# FPGA_Banks_44_45_46_DDR64.net
KiCad netlist of a schematic drawn in Altium Designer
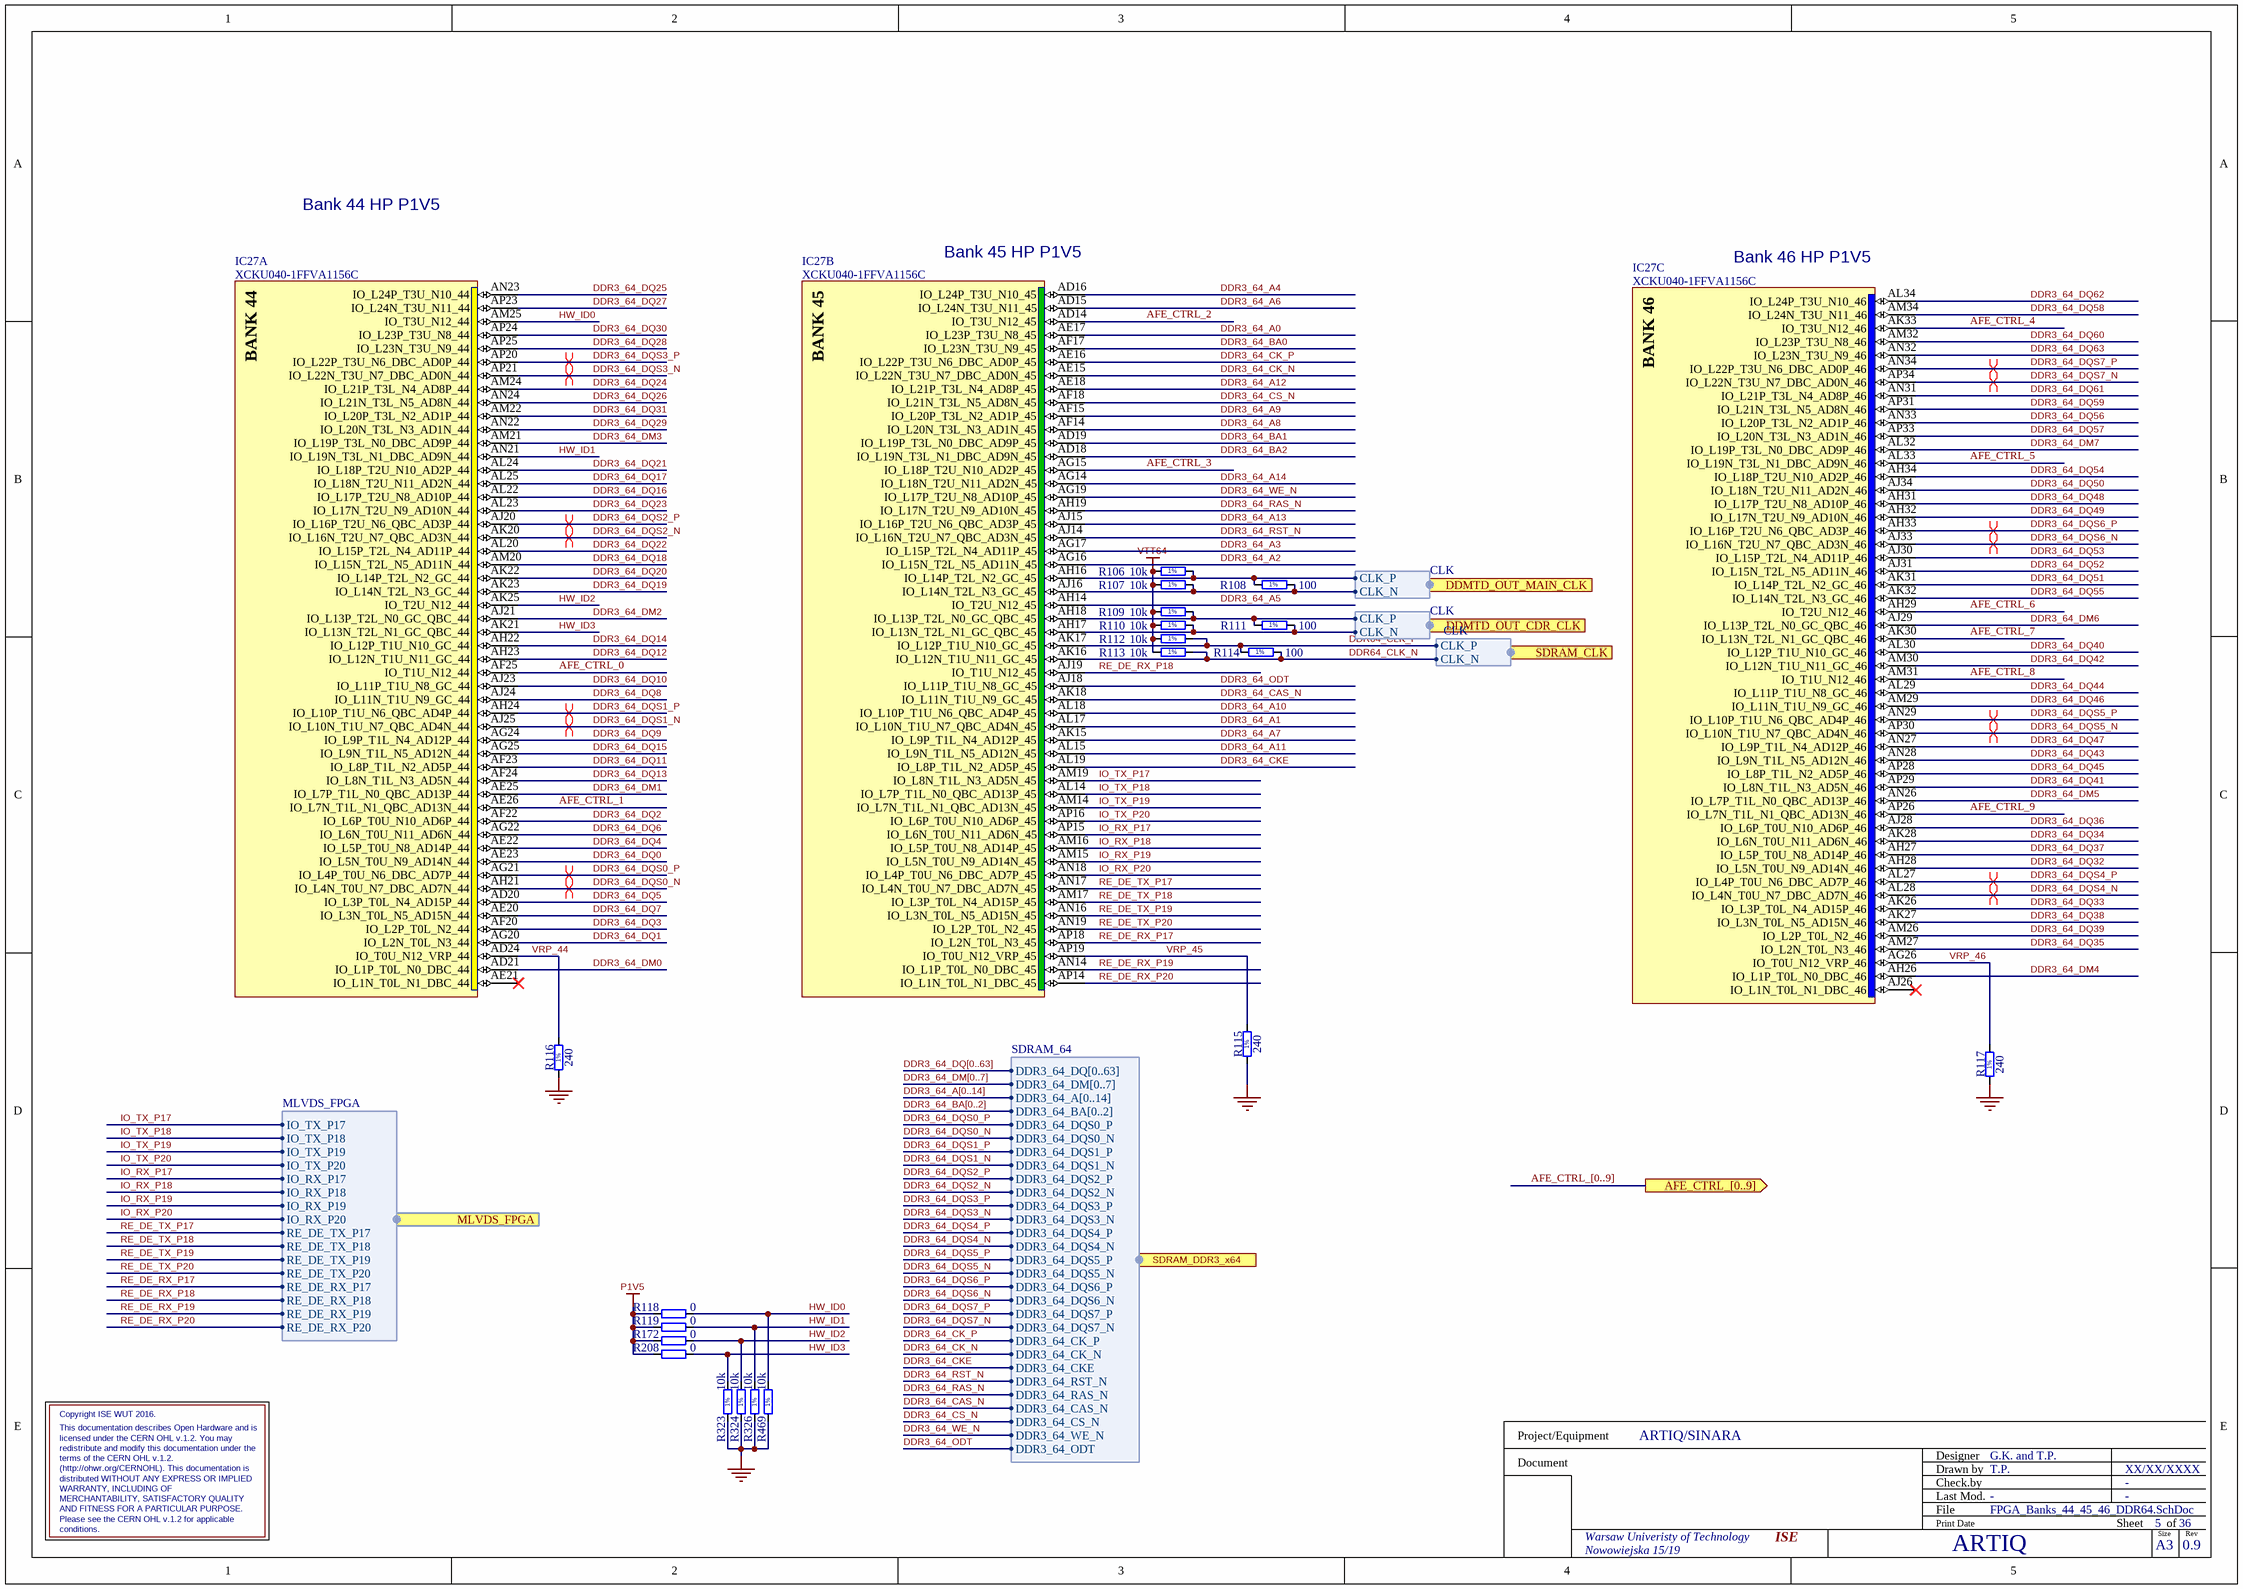
[diagram p0: FPGA_Banks_44_45_46_DDR64.SchDoc]

(export (version "E")
  (design (tool "Eeschema 10.0.6"))
  (components
    (comp (ref "IC27")
      (value "XCKU040-1FFVA1156C")
      (footprint "BGA1156C100P34X34_3500X3500X350")
      (description "Kintex UltraScale FPGA, 520 I/O, 530K Cells, 1156-Ball BGA, Speed Grade 1, Commercial Grade")
      (fields (field (name "MANUFACTURER") "XILINX") (field (name "AUTHOR") "CERN DEM CA"))
      (libsource (lib "ICs And Semiconductors") (part "XCKU040-1FFVA1156C"))
    )
    (comp (ref "R106")
      (value "10k")
      (footprint "RESC1005X40N")
      (description "Resistor - 1%")
      (fields
        (field (name "PART NUMBER") "R0402_10K_1%_0.0625W_100PPM")
        (field (name "TOLERANCE") "±1%")
        (field (name "AUTHOR") "CERN DEM JLC")
      )
      (libsource (lib "Resistors") (part "Resistor - 1%"))
    )
    (comp (ref "R107")
      (value "10k")
      (footprint "RESC1005X40N")
      (description "Resistor - 1%")
      (fields
        (field (name "PART NUMBER") "R0402_10K_1%_0.0625W_100PPM")
        (field (name "TOLERANCE") "±1%")
        (field (name "AUTHOR") "CERN DEM JLC")
      )
      (libsource (lib "Resistors") (part "Resistor - 1%"))
    )
    (comp (ref "R108")
      (value "100")
      (footprint "RESC0603X28N")
      (description "Resistor - 1%")
      (fields
        (field (name "MANUFACTURER PART NUMBER") "R0201_100R_1%_0.05W_200PPM")
        (field (name "MANUFACTURER") "GENERIC")
        (field (name "AUTHOR") "CERN DEM JLC")
      )
      (libsource (lib "Resistors") (part "Resistor - 1%"))
    )
    (comp (ref "R109")
      (value "10k")
      (footprint "RESC1005X40N")
      (description "Resistor - 1%")
      (fields
        (field (name "PART NUMBER") "R0402_10K_1%_0.0625W_100PPM")
        (field (name "TOLERANCE") "±1%")
        (field (name "AUTHOR") "CERN DEM JLC")
      )
      (libsource (lib "Resistors") (part "Resistor - 1%"))
    )
    (comp (ref "R110")
      (value "10k")
      (footprint "RESC1005X40N")
      (description "Resistor - 1%")
      (fields
        (field (name "PART NUMBER") "R0402_10K_1%_0.0625W_100PPM")
        (field (name "TOLERANCE") "±1%")
        (field (name "AUTHOR") "CERN DEM JLC")
      )
      (libsource (lib "Resistors") (part "Resistor - 1%"))
    )
    (comp (ref "R111")
      (value "100")
      (footprint "RESC0603X28N")
      (description "Resistor - 1%")
      (fields
        (field (name "MANUFACTURER PART NUMBER") "R0201_100R_1%_0.05W_200PPM")
        (field (name "MANUFACTURER") "GENERIC")
        (field (name "AUTHOR") "CERN DEM JLC")
      )
      (libsource (lib "Resistors") (part "Resistor - 1%"))
    )
    (comp (ref "R112")
      (value "10k")
      (footprint "RESC1005X40N")
      (description "Resistor - 1%")
      (fields
        (field (name "PART NUMBER") "R0402_10K_1%_0.0625W_100PPM")
        (field (name "TOLERANCE") "±1%")
        (field (name "AUTHOR") "CERN DEM JLC")
      )
      (libsource (lib "Resistors") (part "Resistor - 1%"))
    )
    (comp (ref "R113")
      (value "10k")
      (footprint "RESC1005X40N")
      (description "Resistor - 1%")
      (fields
        (field (name "PART NUMBER") "R0402_10K_1%_0.0625W_100PPM")
        (field (name "TOLERANCE") "±1%")
        (field (name "AUTHOR") "CERN DEM JLC")
      )
      (libsource (lib "Resistors") (part "Resistor - 1%"))
    )
    (comp (ref "R114")
      (value "100")
      (footprint "RESC0603X28N")
      (description "Resistor - 1%")
      (fields
        (field (name "MANUFACTURER PART NUMBER") "R0201_100R_1%_0.05W_200PPM")
        (field (name "MANUFACTURER") "GENERIC")
        (field (name "AUTHOR") "CERN DEM JLC")
      )
      (libsource (lib "Resistors") (part "Resistor - 1%"))
    )
    (comp (ref "R115")
      (value "240")
      (footprint "RESC1005X40N")
      (description "Resistor - 1%")
      (fields
        (field (name "MANUFACTURER PART NUMBER") "R0402_240R_1%_0.0625W_100PPM")
        (field (name "MANUFACTURER") "GENERIC")
        (field (name "AUTHOR") "CERN DEM JLC")
      )
      (libsource (lib "Resistors") (part "Resistor - 1%"))
    )
    (comp (ref "R116")
      (value "240")
      (footprint "RESC1005X40N")
      (description "Resistor - 1%")
      (fields
        (field (name "MANUFACTURER PART NUMBER") "R0402_240R_1%_0.0625W_100PPM")
        (field (name "MANUFACTURER") "GENERIC")
        (field (name "AUTHOR") "CERN DEM JLC")
      )
      (libsource (lib "Resistors") (part "Resistor - 1%"))
    )
    (comp (ref "R117")
      (value "240")
      (footprint "RESC1005X40N")
      (description "Resistor - 1%")
      (fields
        (field (name "MANUFACTURER PART NUMBER") "R0402_240R_1%_0.0625W_100PPM")
        (field (name "MANUFACTURER") "GENERIC")
        (field (name "AUTHOR") "CERN DEM JLC")
      )
      (libsource (lib "Resistors") (part "Resistor - 1%"))
    )
    (comp (ref "R118")
      (value "0")
      (footprint "RESC1005X40N")
      (description "Resistor")
      (fields
        (field (name "MANUFACTURER PART NUMBER") "R0402_0R_JUMPER")
        (field (name "MANUFACTURER") "GENERIC")
        (field (name "AUTHOR") "CERN DEM JLC")
      )
      (libsource (lib "Resistors") (part "Resistor"))
    )
    (comp (ref "R119")
      (value "0")
      (footprint "RESC1005X40N")
      (description "Resistor")
      (fields
        (field (name "MANUFACTURER PART NUMBER") "R0402_0R_JUMPER")
        (field (name "MANUFACTURER") "GENERIC")
        (field (name "AUTHOR") "CERN DEM JLC")
      )
      (libsource (lib "Resistors") (part "Resistor"))
    )
    (comp (ref "R172")
      (value "0")
      (footprint "RESC1005X40N")
      (description "Resistor")
      (fields
        (field (name "MANUFACTURER PART NUMBER") "R0402_0R_JUMPER")
        (field (name "MANUFACTURER") "GENERIC")
        (field (name "AUTHOR") "CERN DEM JLC")
      )
      (libsource (lib "Resistors") (part "Resistor"))
    )
    (comp (ref "R208")
      (value "0")
      (footprint "RESC1005X40N")
      (description "Resistor")
      (fields
        (field (name "MANUFACTURER PART NUMBER") "R0402_0R_JUMPER")
        (field (name "MANUFACTURER") "GENERIC")
        (field (name "AUTHOR") "CERN DEM JLC")
      )
      (libsource (lib "Resistors") (part "Resistor"))
    )
    (comp (ref "R323")
      (value "10k")
      (footprint "RESC1005X40N")
      (description "Resistor - 1%")
      (fields
        (field (name "MANUFACTURER PART NUMBER") "R0402_10K_1%_0.0625W_100PPM")
        (field (name "MANUFACTURER") "GENERIC")
        (field (name "AUTHOR") "CERN DEM JLC")
      )
      (libsource (lib "Resistors") (part "Resistor - 1%"))
    )
    (comp (ref "R324")
      (value "10k")
      (footprint "RESC1005X40N")
      (description "Resistor - 1%")
      (fields
        (field (name "MANUFACTURER PART NUMBER") "R0402_10K_1%_0.0625W_100PPM")
        (field (name "MANUFACTURER") "GENERIC")
        (field (name "AUTHOR") "CERN DEM JLC")
      )
      (libsource (lib "Resistors") (part "Resistor - 1%"))
    )
    (comp (ref "R326")
      (value "10k")
      (footprint "RESC1005X40N")
      (description "Resistor - 1%")
      (fields
        (field (name "MANUFACTURER PART NUMBER") "R0402_10K_1%_0.0625W_100PPM")
        (field (name "MANUFACTURER") "GENERIC")
        (field (name "AUTHOR") "CERN DEM JLC")
      )
      (libsource (lib "Resistors") (part "Resistor - 1%"))
    )
    (comp (ref "R469")
      (value "10k")
      (footprint "RESC1005X40N")
      (description "Resistor - 1%")
      (fields
        (field (name "MANUFACTURER PART NUMBER") "R0402_10K_1%_0.0625W_100PPM")
        (field (name "MANUFACTURER") "GENERIC")
        (field (name "AUTHOR") "CERN DEM JLC")
      )
      (libsource (lib "Resistors") (part "Resistor - 1%"))
    )
  )
  (nets
    (net (code "4") (name "/AFE_CTRL_0") (class "Default")
      (node (ref "IC27") (pin "AF25") (pinfunction "IO_T1U_N12_44_AF25") (pintype "bidirectional"))
    )
    (net (code "5") (name "/AFE_CTRL_1") (class "Default")
      (node (ref "IC27") (pin "AE26") (pinfunction "IO_L7N_T1L_N1_QBC_AD13N_44_AE26") (pintype "bidirectional"))
    )
    (net (code "6") (name "/AFE_CTRL_2") (class "Default")
      (node (ref "IC27") (pin "AD14") (pinfunction "IO_T3U_N12_45_AD14") (pintype "bidirectional"))
    )
    (net (code "7") (name "/AFE_CTRL_3") (class "Default")
      (node (ref "IC27") (pin "AG15") (pinfunction "IO_L18P_T2U_N10_AD2P_45_AG15") (pintype "bidirectional"))
    )
    (net (code "8") (name "/AFE_CTRL_4") (class "Default")
      (node (ref "IC27") (pin "AK33") (pinfunction "IO_T3U_N12_46_AK33") (pintype "bidirectional"))
    )
    (net (code "9") (name "/AFE_CTRL_5") (class "Default")
      (node (ref "IC27") (pin "AL33") (pinfunction "IO_L19N_T3L_N1_DBC_AD9N_46_AL33") (pintype "bidirectional"))
    )
    (net (code "10") (name "/AFE_CTRL_6") (class "Default")
      (node (ref "IC27") (pin "AH29") (pinfunction "IO_T2U_N12_46_AH29") (pintype "bidirectional"))
    )
    (net (code "11") (name "/AFE_CTRL_7") (class "Default")
      (node (ref "IC27") (pin "AK30") (pinfunction "IO_L13N_T2L_N1_GC_QBC_46_AK30") (pintype "bidirectional"))
    )
    (net (code "12") (name "/AFE_CTRL_8") (class "Default")
      (node (ref "IC27") (pin "AM31") (pinfunction "IO_T1U_N12_46_AM31") (pintype "bidirectional"))
    )
    (net (code "13") (name "/AFE_CTRL_9") (class "Default")
      (node (ref "IC27") (pin "AP26") (pinfunction "IO_L7N_T1L_N1_QBC_AD13N_46_AP26") (pintype "bidirectional"))
    )
    (net (code "15") (name "/DDR3_64_A0") (class "Default")
      (node (ref "IC27") (pin "AE17") (pinfunction "IO_L23P_T3U_N8_45_AE17") (pintype "bidirectional"))
    )
    (net (code "16") (name "/DDR3_64_A1") (class "Default")
      (node (ref "IC27") (pin "AL17") (pinfunction "IO_L10N_T1U_N7_QBC_AD4N_45_AL17") (pintype "bidirectional"))
    )
    (net (code "17") (name "/DDR3_64_A2") (class "Default")
      (node (ref "IC27") (pin "AG16") (pinfunction "IO_L15N_T2L_N5_AD11N_45_AG16") (pintype "bidirectional"))
    )
    (net (code "18") (name "/DDR3_64_A3") (class "Default")
      (node (ref "IC27") (pin "AG17") (pinfunction "IO_L15P_T2L_N4_AD11P_45_AG17") (pintype "bidirectional"))
    )
    (net (code "19") (name "/DDR3_64_A4") (class "Default")
      (node (ref "IC27") (pin "AD16") (pinfunction "IO_L24P_T3U_N10_45_AD16") (pintype "bidirectional"))
    )
    (net (code "20") (name "/DDR3_64_A5") (class "Default")
      (node (ref "IC27") (pin "AH14") (pinfunction "IO_T2U_N12_45_AH14") (pintype "bidirectional"))
    )
    (net (code "21") (name "/DDR3_64_A6") (class "Default")
      (node (ref "IC27") (pin "AD15") (pinfunction "IO_L24N_T3U_N11_45_AD15") (pintype "bidirectional"))
    )
    (net (code "22") (name "/DDR3_64_A7") (class "Default")
      (node (ref "IC27") (pin "AK15") (pinfunction "IO_L9P_T1L_N4_AD12P_45_AK15") (pintype "bidirectional"))
    )
    (net (code "23") (name "/DDR3_64_A8") (class "Default")
      (node (ref "IC27") (pin "AF14") (pinfunction "IO_L20N_T3L_N3_AD1N_45_AF14") (pintype "bidirectional"))
    )
    (net (code "24") (name "/DDR3_64_A9") (class "Default")
      (node (ref "IC27") (pin "AF15") (pinfunction "IO_L20P_T3L_N2_AD1P_45_AF15") (pintype "bidirectional"))
    )
    (net (code "25") (name "/DDR3_64_A10") (class "Default")
      (node (ref "IC27") (pin "AL18") (pinfunction "IO_L10P_T1U_N6_QBC_AD4P_45_AL18") (pintype "bidirectional"))
    )
    (net (code "26") (name "/DDR3_64_A11") (class "Default")
      (node (ref "IC27") (pin "AL15") (pinfunction "IO_L9N_T1L_N5_AD12N_45_AL15") (pintype "bidirectional"))
    )
    (net (code "27") (name "/DDR3_64_A12") (class "Default")
      (node (ref "IC27") (pin "AE18") (pinfunction "IO_L21P_T3L_N4_AD8P_45_AE18") (pintype "bidirectional"))
    )
    (net (code "28") (name "/DDR3_64_A13") (class "Default")
      (node (ref "IC27") (pin "AJ15") (pinfunction "IO_L16P_T2U_N6_QBC_AD3P_45_AJ15") (pintype "bidirectional"))
    )
    (net (code "29") (name "/DDR3_64_A14") (class "Default")
      (node (ref "IC27") (pin "AG14") (pinfunction "IO_L18N_T2U_N11_AD2N_45_AG14") (pintype "bidirectional"))
    )
    (net (code "31") (name "/DDR3_64_BA0") (class "Default")
      (node (ref "IC27") (pin "AF17") (pinfunction "IO_L23N_T3U_N9_45_AF17") (pintype "bidirectional"))
    )
    (net (code "32") (name "/DDR3_64_BA1") (class "Default")
      (node (ref "IC27") (pin "AD19") (pinfunction "IO_L19P_T3L_N0_DBC_AD9P_45_AD19") (pintype "bidirectional"))
    )
    (net (code "33") (name "/DDR3_64_BA2") (class "Default")
      (node (ref "IC27") (pin "AD18") (pinfunction "IO_L19N_T3L_N1_DBC_AD9N_45_AD18") (pintype "bidirectional"))
    )
    (net (code "34") (name "/DDR3_64_CAS_N") (class "Default")
      (node (ref "IC27") (pin "AK18") (pinfunction "IO_L11N_T1U_N9_GC_45_AK18") (pintype "bidirectional"))
    )
    (net (code "35") (name "/DDR3_64_CKE") (class "Default")
      (node (ref "IC27") (pin "AL19") (pinfunction "IO_L8P_T1L_N2_AD5P_45_AL19") (pintype "bidirectional"))
    )
    (net (code "36") (name "/DDR3_64_CK_N") (class "Default")
      (node (ref "IC27") (pin "AE15") (pinfunction "IO_L22N_T3U_N7_DBC_AD0N_45_AE15") (pintype "bidirectional"))
    )
    (net (code "37") (name "/DDR3_64_CK_P") (class "Default")
      (node (ref "IC27") (pin "AE16") (pinfunction "IO_L22P_T3U_N6_DBC_AD0P_45_AE16") (pintype "bidirectional"))
    )
    (net (code "38") (name "/DDR3_64_CS_N") (class "Default")
      (node (ref "IC27") (pin "AF18") (pinfunction "IO_L21N_T3L_N5_AD8N_45_AF18") (pintype "bidirectional"))
    )
    (net (code "39") (name "/DDR3_64_DM0") (class "Default")
      (node (ref "IC27") (pin "AD21") (pinfunction "IO_L1P_T0L_N0_DBC_44_AD21") (pintype "bidirectional"))
    )
    (net (code "40") (name "/DDR3_64_DM1") (class "Default")
      (node (ref "IC27") (pin "AE25") (pinfunction "IO_L7P_T1L_N0_QBC_AD13P_44_AE25") (pintype "bidirectional"))
    )
    (net (code "41") (name "/DDR3_64_DM2") (class "Default")
      (node (ref "IC27") (pin "AJ21") (pinfunction "IO_L13P_T2L_N0_GC_QBC_44_AJ21") (pintype "bidirectional"))
    )
    (net (code "42") (name "/DDR3_64_DM3") (class "Default")
      (node (ref "IC27") (pin "AM21") (pinfunction "IO_L19P_T3L_N0_DBC_AD9P_44_AM21") (pintype "bidirectional"))
    )
    (net (code "43") (name "/DDR3_64_DM4") (class "Default")
      (node (ref "IC27") (pin "AH26") (pinfunction "IO_L1P_T0L_N0_DBC_46_AH26") (pintype "bidirectional"))
    )
    (net (code "44") (name "/DDR3_64_DM5") (class "Default")
      (node (ref "IC27") (pin "AN26") (pinfunction "IO_L7P_T1L_N0_QBC_AD13P_46_AN26") (pintype "bidirectional"))
    )
    (net (code "45") (name "/DDR3_64_DM6") (class "Default")
      (node (ref "IC27") (pin "AJ29") (pinfunction "IO_L13P_T2L_N0_GC_QBC_46_AJ29") (pintype "bidirectional"))
    )
    (net (code "46") (name "/DDR3_64_DM7") (class "Default")
      (node (ref "IC27") (pin "AL32") (pinfunction "IO_L19P_T3L_N0_DBC_AD9P_46_AL32") (pintype "bidirectional"))
    )
    (net (code "48") (name "/DDR3_64_DQ0") (class "Default")
      (node (ref "IC27") (pin "AE23") (pinfunction "IO_L5N_T0U_N9_AD14N_44_AE23") (pintype "bidirectional"))
    )
    (net (code "49") (name "/DDR3_64_DQ1") (class "Default")
      (node (ref "IC27") (pin "AG20") (pinfunction "IO_L2N_T0L_N3_44_AG20") (pintype "bidirectional"))
    )
    (net (code "50") (name "/DDR3_64_DQ2") (class "Default")
      (node (ref "IC27") (pin "AF22") (pinfunction "IO_L6P_T0U_N10_AD6P_44_AF22") (pintype "bidirectional"))
    )
    (net (code "51") (name "/DDR3_64_DQ3") (class "Default")
      (node (ref "IC27") (pin "AF20") (pinfunction "IO_L2P_T0L_N2_44_AF20") (pintype "bidirectional"))
    )
    (net (code "52") (name "/DDR3_64_DQ4") (class "Default")
      (node (ref "IC27") (pin "AE22") (pinfunction "IO_L5P_T0U_N8_AD14P_44_AE22") (pintype "bidirectional"))
    )
    (net (code "53") (name "/DDR3_64_DQ5") (class "Default")
      (node (ref "IC27") (pin "AD20") (pinfunction "IO_L3P_T0L_N4_AD15P_44_AD20") (pintype "bidirectional"))
    )
    (net (code "54") (name "/DDR3_64_DQ6") (class "Default")
      (node (ref "IC27") (pin "AG22") (pinfunction "IO_L6N_T0U_N11_AD6N_44_AG22") (pintype "bidirectional"))
    )
    (net (code "55") (name "/DDR3_64_DQ7") (class "Default")
      (node (ref "IC27") (pin "AE20") (pinfunction "IO_L3N_T0L_N5_AD15N_44_AE20") (pintype "bidirectional"))
    )
    (net (code "56") (name "/DDR3_64_DQ8") (class "Default")
      (node (ref "IC27") (pin "AJ24") (pinfunction "IO_L11N_T1U_N9_GC_44_AJ24") (pintype "bidirectional"))
    )
    (net (code "57") (name "/DDR3_64_DQ9") (class "Default")
      (node (ref "IC27") (pin "AG24") (pinfunction "IO_L9P_T1L_N4_AD12P_44_AG24") (pintype "bidirectional"))
    )
    (net (code "58") (name "/DDR3_64_DQ10") (class "Default")
      (node (ref "IC27") (pin "AJ23") (pinfunction "IO_L11P_T1U_N8_GC_44_AJ23") (pintype "bidirectional"))
    )
    (net (code "59") (name "/DDR3_64_DQ11") (class "Default")
      (node (ref "IC27") (pin "AF23") (pinfunction "IO_L8P_T1L_N2_AD5P_44_AF23") (pintype "bidirectional"))
    )
    (net (code "60") (name "/DDR3_64_DQ12") (class "Default")
      (node (ref "IC27") (pin "AH23") (pinfunction "IO_L12N_T1U_N11_GC_44_AH23") (pintype "bidirectional"))
    )
    (net (code "61") (name "/DDR3_64_DQ13") (class "Default")
      (node (ref "IC27") (pin "AF24") (pinfunction "IO_L8N_T1L_N3_AD5N_44_AF24") (pintype "bidirectional"))
    )
    (net (code "62") (name "/DDR3_64_DQ14") (class "Default")
      (node (ref "IC27") (pin "AH22") (pinfunction "IO_L12P_T1U_N10_GC_44_AH22") (pintype "bidirectional"))
    )
    (net (code "63") (name "/DDR3_64_DQ15") (class "Default")
      (node (ref "IC27") (pin "AG25") (pinfunction "IO_L9N_T1L_N5_AD12N_44_AG25") (pintype "bidirectional"))
    )
    (net (code "64") (name "/DDR3_64_DQ16") (class "Default")
      (node (ref "IC27") (pin "AL22") (pinfunction "IO_L17P_T2U_N8_AD10P_44_AL22") (pintype "bidirectional"))
    )
    (net (code "65") (name "/DDR3_64_DQ17") (class "Default")
      (node (ref "IC27") (pin "AL25") (pinfunction "IO_L18N_T2U_N11_AD2N_44_AL25") (pintype "bidirectional"))
    )
    (net (code "66") (name "/DDR3_64_DQ18") (class "Default")
      (node (ref "IC27") (pin "AM20") (pinfunction "IO_L15N_T2L_N5_AD11N_44_AM20") (pintype "bidirectional"))
    )
    (net (code "67") (name "/DDR3_64_DQ19") (class "Default")
      (node (ref "IC27") (pin "AK23") (pinfunction "IO_L14N_T2L_N3_GC_44_AK23") (pintype "bidirectional"))
    )
    (net (code "68") (name "/DDR3_64_DQ20") (class "Default")
      (node (ref "IC27") (pin "AK22") (pinfunction "IO_L14P_T2L_N2_GC_44_AK22") (pintype "bidirectional"))
    )
    (net (code "69") (name "/DDR3_64_DQ21") (class "Default")
      (node (ref "IC27") (pin "AL24") (pinfunction "IO_L18P_T2U_N10_AD2P_44_AL24") (pintype "bidirectional"))
    )
    (net (code "70") (name "/DDR3_64_DQ22") (class "Default")
      (node (ref "IC27") (pin "AL20") (pinfunction "IO_L15P_T2L_N4_AD11P_44_AL20") (pintype "bidirectional"))
    )
    (net (code "71") (name "/DDR3_64_DQ23") (class "Default")
      (node (ref "IC27") (pin "AL23") (pinfunction "IO_L17N_T2U_N9_AD10N_44_AL23") (pintype "bidirectional"))
    )
    (net (code "72") (name "/DDR3_64_DQ24") (class "Default")
      (node (ref "IC27") (pin "AM24") (pinfunction "IO_L21P_T3L_N4_AD8P_44_AM24") (pintype "bidirectional"))
    )
    (net (code "73") (name "/DDR3_64_DQ25") (class "Default")
      (node (ref "IC27") (pin "AN23") (pinfunction "IO_L24P_T3U_N10_44_AN23") (pintype "bidirectional"))
    )
    (net (code "74") (name "/DDR3_64_DQ26") (class "Default")
      (node (ref "IC27") (pin "AN24") (pinfunction "IO_L21N_T3L_N5_AD8N_44_AN24") (pintype "bidirectional"))
    )
    (net (code "75") (name "/DDR3_64_DQ27") (class "Default")
      (node (ref "IC27") (pin "AP23") (pinfunction "IO_L24N_T3U_N11_44_AP23") (pintype "bidirectional"))
    )
    (net (code "76") (name "/DDR3_64_DQ28") (class "Default")
      (node (ref "IC27") (pin "AP25") (pinfunction "IO_L23N_T3U_N9_44_AP25") (pintype "bidirectional"))
    )
    (net (code "77") (name "/DDR3_64_DQ29") (class "Default")
      (node (ref "IC27") (pin "AN22") (pinfunction "IO_L20N_T3L_N3_AD1N_44_AN22") (pintype "bidirectional"))
    )
    (net (code "78") (name "/DDR3_64_DQ30") (class "Default")
      (node (ref "IC27") (pin "AP24") (pinfunction "IO_L23P_T3U_N8_44_AP24") (pintype "bidirectional"))
    )
    (net (code "79") (name "/DDR3_64_DQ31") (class "Default")
      (node (ref "IC27") (pin "AM22") (pinfunction "IO_L20P_T3L_N2_AD1P_44_AM22") (pintype "bidirectional"))
    )
    (net (code "80") (name "/DDR3_64_DQ32") (class "Default")
      (node (ref "IC27") (pin "AH28") (pinfunction "IO_L5N_T0U_N9_AD14N_46_AH28") (pintype "bidirectional"))
    )
    (net (code "81") (name "/DDR3_64_DQ33") (class "Default")
      (node (ref "IC27") (pin "AK26") (pinfunction "IO_L3P_T0L_N4_AD15P_46_AK26") (pintype "bidirectional"))
    )
    (net (code "82") (name "/DDR3_64_DQ34") (class "Default")
      (node (ref "IC27") (pin "AK28") (pinfunction "IO_L6N_T0U_N11_AD6N_46_AK28") (pintype "bidirectional"))
    )
    (net (code "83") (name "/DDR3_64_DQ35") (class "Default")
      (node (ref "IC27") (pin "AM27") (pinfunction "IO_L2N_T0L_N3_46_AM27") (pintype "bidirectional"))
    )
    (net (code "84") (name "/DDR3_64_DQ36") (class "Default")
      (node (ref "IC27") (pin "AJ28") (pinfunction "IO_L6P_T0U_N10_AD6P_46_AJ28") (pintype "bidirectional"))
    )
    (net (code "85") (name "/DDR3_64_DQ37") (class "Default")
      (node (ref "IC27") (pin "AH27") (pinfunction "IO_L5P_T0U_N8_AD14P_46_AH27") (pintype "bidirectional"))
    )
    (net (code "86") (name "/DDR3_64_DQ38") (class "Default")
      (node (ref "IC27") (pin "AK27") (pinfunction "IO_L3N_T0L_N5_AD15N_46_AK27") (pintype "bidirectional"))
    )
    (net (code "87") (name "/DDR3_64_DQ39") (class "Default")
      (node (ref "IC27") (pin "AM26") (pinfunction "IO_L2P_T0L_N2_46_AM26") (pintype "bidirectional"))
    )
    (net (code "88") (name "/DDR3_64_DQ40") (class "Default")
      (node (ref "IC27") (pin "AL30") (pinfunction "IO_L12P_T1U_N10_GC_46_AL30") (pintype "bidirectional"))
    )
    (net (code "89") (name "/DDR3_64_DQ41") (class "Default")
      (node (ref "IC27") (pin "AP29") (pinfunction "IO_L8N_T1L_N3_AD5N_46_AP29") (pintype "bidirectional"))
    )
    (net (code "90") (name "/DDR3_64_DQ42") (class "Default")
      (node (ref "IC27") (pin "AM30") (pinfunction "IO_L12N_T1U_N11_GC_46_AM30") (pintype "bidirectional"))
    )
    (net (code "91") (name "/DDR3_64_DQ43") (class "Default")
      (node (ref "IC27") (pin "AN28") (pinfunction "IO_L9N_T1L_N5_AD12N_46_AN28") (pintype "bidirectional"))
    )
    (net (code "92") (name "/DDR3_64_DQ44") (class "Default")
      (node (ref "IC27") (pin "AL29") (pinfunction "IO_L11P_T1U_N8_GC_46_AL29") (pintype "bidirectional"))
    )
    (net (code "93") (name "/DDR3_64_DQ45") (class "Default")
      (node (ref "IC27") (pin "AP28") (pinfunction "IO_L8P_T1L_N2_AD5P_46_AP28") (pintype "bidirectional"))
    )
    (net (code "94") (name "/DDR3_64_DQ46") (class "Default")
      (node (ref "IC27") (pin "AM29") (pinfunction "IO_L11N_T1U_N9_GC_46_AM29") (pintype "bidirectional"))
    )
    (net (code "95") (name "/DDR3_64_DQ47") (class "Default")
      (node (ref "IC27") (pin "AN27") (pinfunction "IO_L9P_T1L_N4_AD12P_46_AN27") (pintype "bidirectional"))
    )
    (net (code "96") (name "/DDR3_64_DQ48") (class "Default")
      (node (ref "IC27") (pin "AH31") (pinfunction "IO_L17P_T2U_N8_AD10P_46_AH31") (pintype "bidirectional"))
    )
    (net (code "97") (name "/DDR3_64_DQ49") (class "Default")
      (node (ref "IC27") (pin "AH32") (pinfunction "IO_L17N_T2U_N9_AD10N_46_AH32") (pintype "bidirectional"))
    )
    (net (code "98") (name "/DDR3_64_DQ50") (class "Default")
      (node (ref "IC27") (pin "AJ34") (pinfunction "IO_L18N_T2U_N11_AD2N_46_AJ34") (pintype "bidirectional"))
    )
    (net (code "99") (name "/DDR3_64_DQ51") (class "Default")
      (node (ref "IC27") (pin "AK31") (pinfunction "IO_L14P_T2L_N2_GC_46_AK31") (pintype "bidirectional"))
    )
    (net (code "100") (name "/DDR3_64_DQ52") (class "Default")
      (node (ref "IC27") (pin "AJ31") (pinfunction "IO_L15N_T2L_N5_AD11N_46_AJ31") (pintype "bidirectional"))
    )
    (net (code "101") (name "/DDR3_64_DQ53") (class "Default")
      (node (ref "IC27") (pin "AJ30") (pinfunction "IO_L15P_T2L_N4_AD11P_46_AJ30") (pintype "bidirectional"))
    )
    (net (code "102") (name "/DDR3_64_DQ54") (class "Default")
      (node (ref "IC27") (pin "AH34") (pinfunction "IO_L18P_T2U_N10_AD2P_46_AH34") (pintype "bidirectional"))
    )
    (net (code "103") (name "/DDR3_64_DQ55") (class "Default")
      (node (ref "IC27") (pin "AK32") (pinfunction "IO_L14N_T2L_N3_GC_46_AK32") (pintype "bidirectional"))
    )
    (net (code "104") (name "/DDR3_64_DQ56") (class "Default")
      (node (ref "IC27") (pin "AN33") (pinfunction "IO_L20P_T3L_N2_AD1P_46_AN33") (pintype "bidirectional"))
    )
    (net (code "105") (name "/DDR3_64_DQ57") (class "Default")
      (node (ref "IC27") (pin "AP33") (pinfunction "IO_L20N_T3L_N3_AD1N_46_AP33") (pintype "bidirectional"))
    )
    (net (code "106") (name "/DDR3_64_DQ58") (class "Default")
      (node (ref "IC27") (pin "AM34") (pinfunction "IO_L24N_T3U_N11_46_AM34") (pintype "bidirectional"))
    )
    (net (code "107") (name "/DDR3_64_DQ59") (class "Default")
      (node (ref "IC27") (pin "AP31") (pinfunction "IO_L21N_T3L_N5_AD8N_46_AP31") (pintype "bidirectional"))
    )
    (net (code "108") (name "/DDR3_64_DQ60") (class "Default")
      (node (ref "IC27") (pin "AM32") (pinfunction "IO_L23P_T3U_N8_46_AM32") (pintype "bidirectional"))
    )
    (net (code "109") (name "/DDR3_64_DQ61") (class "Default")
      (node (ref "IC27") (pin "AN31") (pinfunction "IO_L21P_T3L_N4_AD8P_46_AN31") (pintype "bidirectional"))
    )
    (net (code "110") (name "/DDR3_64_DQ62") (class "Default")
      (node (ref "IC27") (pin "AL34") (pinfunction "IO_L24P_T3U_N10_46_AL34") (pintype "bidirectional"))
    )
    (net (code "111") (name "/DDR3_64_DQ63") (class "Default")
      (node (ref "IC27") (pin "AN32") (pinfunction "IO_L23N_T3U_N9_46_AN32") (pintype "bidirectional"))
    )
    (net (code "112") (name "/DDR3_64_DQS0_N") (class "Default")
      (node (ref "IC27") (pin "AH21") (pinfunction "IO_L4N_T0U_N7_DBC_AD7N_44_AH21") (pintype "bidirectional"))
    )
    (net (code "113") (name "/DDR3_64_DQS0_P") (class "Default")
      (node (ref "IC27") (pin "AG21") (pinfunction "IO_L4P_T0U_N6_DBC_AD7P_44_AG21") (pintype "bidirectional"))
    )
    (net (code "114") (name "/DDR3_64_DQS1_N") (class "Default")
      (node (ref "IC27") (pin "AJ25") (pinfunction "IO_L10N_T1U_N7_QBC_AD4N_44_AJ25") (pintype "bidirectional"))
    )
    (net (code "115") (name "/DDR3_64_DQS1_P") (class "Default")
      (node (ref "IC27") (pin "AH24") (pinfunction "IO_L10P_T1U_N6_QBC_AD4P_44_AH24") (pintype "bidirectional"))
    )
    (net (code "116") (name "/DDR3_64_DQS2_N") (class "Default")
      (node (ref "IC27") (pin "AK20") (pinfunction "IO_L16N_T2U_N7_QBC_AD3N_44_AK20") (pintype "bidirectional"))
    )
    (net (code "117") (name "/DDR3_64_DQS2_P") (class "Default")
      (node (ref "IC27") (pin "AJ20") (pinfunction "IO_L16P_T2U_N6_QBC_AD3P_44_AJ20") (pintype "bidirectional"))
    )
    (net (code "118") (name "/DDR3_64_DQS3_N") (class "Default")
      (node (ref "IC27") (pin "AP21") (pinfunction "IO_L22N_T3U_N7_DBC_AD0N_44_AP21") (pintype "bidirectional"))
    )
    (net (code "119") (name "/DDR3_64_DQS3_P") (class "Default")
      (node (ref "IC27") (pin "AP20") (pinfunction "IO_L22P_T3U_N6_DBC_AD0P_44_AP20") (pintype "bidirectional"))
    )
    (net (code "120") (name "/DDR3_64_DQS4_N") (class "Default")
      (node (ref "IC27") (pin "AL28") (pinfunction "IO_L4N_T0U_N7_DBC_AD7N_46_AL28") (pintype "bidirectional"))
    )
    (net (code "121") (name "/DDR3_64_DQS4_P") (class "Default")
      (node (ref "IC27") (pin "AL27") (pinfunction "IO_L4P_T0U_N6_DBC_AD7P_46_AL27") (pintype "bidirectional"))
    )
    (net (code "122") (name "/DDR3_64_DQS5_N") (class "Default")
      (node (ref "IC27") (pin "AP30") (pinfunction "IO_L10N_T1U_N7_QBC_AD4N_46_AP30") (pintype "bidirectional"))
    )
    (net (code "123") (name "/DDR3_64_DQS5_P") (class "Default")
      (node (ref "IC27") (pin "AN29") (pinfunction "IO_L10P_T1U_N6_QBC_AD4P_46_AN29") (pintype "bidirectional"))
    )
    (net (code "124") (name "/DDR3_64_DQS6_N") (class "Default")
      (node (ref "IC27") (pin "AJ33") (pinfunction "IO_L16N_T2U_N7_QBC_AD3N_46_AJ33") (pintype "bidirectional"))
    )
    (net (code "125") (name "/DDR3_64_DQS6_P") (class "Default")
      (node (ref "IC27") (pin "AH33") (pinfunction "IO_L16P_T2U_N6_QBC_AD3P_46_AH33") (pintype "bidirectional"))
    )
    (net (code "126") (name "/DDR3_64_DQS7_N") (class "Default")
      (node (ref "IC27") (pin "AP34") (pinfunction "IO_L22N_T3U_N7_DBC_AD0N_46_AP34") (pintype "bidirectional"))
    )
    (net (code "127") (name "/DDR3_64_DQS7_P") (class "Default")
      (node (ref "IC27") (pin "AN34") (pinfunction "IO_L22P_T3U_N6_DBC_AD0P_46_AN34") (pintype "bidirectional"))
    )
    (net (code "129") (name "/DDR3_64_ODT") (class "Default")
      (node (ref "IC27") (pin "AJ18") (pinfunction "IO_L11P_T1U_N8_GC_45_AJ18") (pintype "bidirectional"))
    )
    (net (code "130") (name "/DDR3_64_RAS_N") (class "Default")
      (node (ref "IC27") (pin "AH19") (pinfunction "IO_L17N_T2U_N9_AD10N_45_AH19") (pintype "bidirectional"))
    )
    (net (code "131") (name "/DDR3_64_RST_N") (class "Default")
      (node (ref "IC27") (pin "AJ14") (pinfunction "IO_L16N_T2U_N7_QBC_AD3N_45_AJ14") (pintype "bidirectional"))
    )
    (net (code "132") (name "/DDR3_64_WE_N") (class "Default")
      (node (ref "IC27") (pin "AG19") (pinfunction "IO_L17P_T2U_N8_AD10P_45_AG19") (pintype "bidirectional"))
    )
    (net (code "133") (name "/DDR64_CLK_N") (class "Default")
      (node (ref "IC27") (pin "AK16") (pinfunction "IO_L12N_T1U_N11_GC_45_AK16") (pintype "bidirectional"))
      (node (ref "R113") (pin "2") (pinfunction "2_2") (pintype "passive"))
      (node (ref "R114") (pin "2") (pinfunction "2_2") (pintype "passive"))
    )
    (net (code "134") (name "/DDR64_CLK_P") (class "Default")
      (node (ref "IC27") (pin "AK17") (pinfunction "IO_L12P_T1U_N10_GC_45_AK17") (pintype "bidirectional"))
      (node (ref "R112") (pin "2") (pinfunction "2_2") (pintype "passive"))
      (node (ref "R114") (pin "1") (pinfunction "1_1") (pintype "passive"))
    )
    (net (code "135") (name "/HW_ID0") (class "Default")
      (node (ref "IC27") (pin "AM25") (pinfunction "IO_T3U_N12_44_AM25") (pintype "bidirectional"))
      (node (ref "R118") (pin "2") (pinfunction "2_2") (pintype "passive"))
      (node (ref "R469") (pin "2") (pinfunction "2_2") (pintype "passive"))
    )
    (net (code "136") (name "/HW_ID1") (class "Default")
      (node (ref "IC27") (pin "AN21") (pinfunction "IO_L19N_T3L_N1_DBC_AD9N_44_AN21") (pintype "bidirectional"))
      (node (ref "R119") (pin "2") (pinfunction "2_2") (pintype "passive"))
      (node (ref "R326") (pin "2") (pinfunction "2_2") (pintype "passive"))
    )
    (net (code "137") (name "/HW_ID2") (class "Default")
      (node (ref "IC27") (pin "AK25") (pinfunction "IO_T2U_N12_44_AK25") (pintype "bidirectional"))
      (node (ref "R172") (pin "2") (pinfunction "2_2") (pintype "passive"))
      (node (ref "R324") (pin "2") (pinfunction "2_2") (pintype "passive"))
    )
    (net (code "138") (name "/HW_ID3") (class "Default")
      (node (ref "IC27") (pin "AK21") (pinfunction "IO_L13N_T2L_N1_GC_QBC_44_AK21") (pintype "bidirectional"))
      (node (ref "R208") (pin "2") (pinfunction "2_2") (pintype "passive"))
      (node (ref "R323") (pin "2") (pinfunction "2_2") (pintype "passive"))
    )
    (net (code "139") (name "/IO_RX_P17") (class "Default")
      (node (ref "IC27") (pin "AP15") (pinfunction "IO_L6N_T0U_N11_AD6N_45_AP15") (pintype "bidirectional"))
    )
    (net (code "140") (name "/IO_RX_P18") (class "Default")
      (node (ref "IC27") (pin "AM16") (pinfunction "IO_L5P_T0U_N8_AD14P_45_AM16") (pintype "bidirectional"))
    )
    (net (code "141") (name "/IO_RX_P19") (class "Default")
      (node (ref "IC27") (pin "AM15") (pinfunction "IO_L5N_T0U_N9_AD14N_45_AM15") (pintype "bidirectional"))
    )
    (net (code "142") (name "/IO_RX_P20") (class "Default")
      (node (ref "IC27") (pin "AN18") (pinfunction "IO_L4P_T0U_N6_DBC_AD7P_45_AN18") (pintype "bidirectional"))
    )
    (net (code "143") (name "/IO_TX_P17") (class "Default")
      (node (ref "IC27") (pin "AM19") (pinfunction "IO_L8N_T1L_N3_AD5N_45_AM19") (pintype "bidirectional"))
    )
    (net (code "144") (name "/IO_TX_P18") (class "Default")
      (node (ref "IC27") (pin "AL14") (pinfunction "IO_L7P_T1L_N0_QBC_AD13P_45_AL14") (pintype "bidirectional"))
    )
    (net (code "145") (name "/IO_TX_P19") (class "Default")
      (node (ref "IC27") (pin "AM14") (pinfunction "IO_L7N_T1L_N1_QBC_AD13N_45_AM14") (pintype "bidirectional"))
    )
    (net (code "146") (name "/IO_TX_P20") (class "Default")
      (node (ref "IC27") (pin "AP16") (pinfunction "IO_L6P_T0U_N10_AD6P_45_AP16") (pintype "bidirectional"))
    )
    (net (code "147") (name "/RE_DE_RX_P17") (class "Default")
      (node (ref "IC27") (pin "AP18") (pinfunction "IO_L2N_T0L_N3_45_AP18") (pintype "bidirectional"))
    )
    (net (code "148") (name "/RE_DE_RX_P18") (class "Default")
      (node (ref "IC27") (pin "AJ19") (pinfunction "IO_T1U_N12_45_AJ19") (pintype "bidirectional"))
    )
    (net (code "149") (name "/RE_DE_RX_P19") (class "Default")
      (node (ref "IC27") (pin "AN14") (pinfunction "IO_L1P_T0L_N0_DBC_45_AN14") (pintype "bidirectional"))
    )
    (net (code "150") (name "/RE_DE_RX_P20") (class "Default")
      (node (ref "IC27") (pin "AP14") (pinfunction "IO_L1N_T0L_N1_DBC_45_AP14") (pintype "bidirectional"))
    )
    (net (code "151") (name "/RE_DE_TX_P17") (class "Default")
      (node (ref "IC27") (pin "AN17") (pinfunction "IO_L4N_T0U_N7_DBC_AD7N_45_AN17") (pintype "bidirectional"))
    )
    (net (code "152") (name "/RE_DE_TX_P18") (class "Default")
      (node (ref "IC27") (pin "AM17") (pinfunction "IO_L3P_T0L_N4_AD15P_45_AM17") (pintype "bidirectional"))
    )
    (net (code "153") (name "/RE_DE_TX_P19") (class "Default")
      (node (ref "IC27") (pin "AN16") (pinfunction "IO_L3N_T0L_N5_AD15N_45_AN16") (pintype "bidirectional"))
    )
    (net (code "154") (name "/RE_DE_TX_P20") (class "Default")
      (node (ref "IC27") (pin "AN19") (pinfunction "IO_L2P_T0L_N2_45_AN19") (pintype "bidirectional"))
    )
    (net (code "156") (name "/VRP_44") (class "Default")
      (node (ref "IC27") (pin "AD24") (pinfunction "IO_T0U_N12_VRP_44_AD24") (pintype "bidirectional"))
      (node (ref "R116") (pin "2") (pinfunction "2_2") (pintype "passive"))
    )
    (net (code "157") (name "/VRP_45") (class "Default")
      (node (ref "IC27") (pin "AP19") (pinfunction "IO_T0U_N12_VRP_45_AP19") (pintype "bidirectional"))
      (node (ref "R115") (pin "2") (pinfunction "2_2") (pintype "passive"))
    )
    (net (code "158") (name "/VRP_46") (class "Default")
      (node (ref "IC27") (pin "AG26") (pinfunction "IO_T0U_N12_VRP_46_AG26") (pintype "bidirectional"))
      (node (ref "R117") (pin "2") (pinfunction "2_2") (pintype "passive"))
    )
    (net (code "162") (name "GND") (class "Default")
      (node (ref "R115") (pin "1") (pinfunction "1_1") (pintype "passive"))
      (node (ref "R116") (pin "1") (pinfunction "1_1") (pintype "passive"))
      (node (ref "R117") (pin "1") (pinfunction "1_1") (pintype "passive"))
      (node (ref "R323") (pin "1") (pinfunction "1_1") (pintype "passive"))
      (node (ref "R324") (pin "1") (pinfunction "1_1") (pintype "passive"))
      (node (ref "R326") (pin "1") (pinfunction "1_1") (pintype "passive"))
      (node (ref "R469") (pin "1") (pinfunction "1_1") (pintype "passive"))
    )
    (net (code "163") (name "Net-(IC27B-IO_L13N_T2L_N1_GC_QBC_45)") (class "Default")
      (node (ref "IC27") (pin "AH17") (pinfunction "IO_L13N_T2L_N1_GC_QBC_45_AH17") (pintype "bidirectional"))
      (node (ref "R110") (pin "2") (pinfunction "2_2") (pintype "passive"))
      (node (ref "R111") (pin "2") (pinfunction "2_2") (pintype "passive"))
    )
    (net (code "164") (name "Net-(IC27B-IO_L13P_T2L_N0_GC_QBC_45)") (class "Default")
      (node (ref "IC27") (pin "AH18") (pinfunction "IO_L13P_T2L_N0_GC_QBC_45_AH18") (pintype "bidirectional"))
      (node (ref "R109") (pin "2") (pinfunction "2_2") (pintype "passive"))
      (node (ref "R111") (pin "1") (pinfunction "1_1") (pintype "passive"))
    )
    (net (code "165") (name "Net-(IC27B-IO_L14N_T2L_N3_GC_45)") (class "Default")
      (node (ref "IC27") (pin "AJ16") (pinfunction "IO_L14N_T2L_N3_GC_45_AJ16") (pintype "bidirectional"))
      (node (ref "R107") (pin "2") (pinfunction "2_2") (pintype "passive"))
      (node (ref "R108") (pin "2") (pinfunction "2_2") (pintype "passive"))
    )
    (net (code "166") (name "Net-(IC27B-IO_L14P_T2L_N2_GC_45)") (class "Default")
      (node (ref "IC27") (pin "AH16") (pinfunction "IO_L14P_T2L_N2_GC_45_AH16") (pintype "bidirectional"))
      (node (ref "R106") (pin "2") (pinfunction "2_2") (pintype "passive"))
      (node (ref "R108") (pin "1") (pinfunction "1_1") (pintype "passive"))
    )
    (net (code "167") (name "P1V5") (class "Default")
      (node (ref "R118") (pin "1") (pinfunction "1_1") (pintype "passive"))
      (node (ref "R119") (pin "1") (pinfunction "1_1") (pintype "passive"))
      (node (ref "R172") (pin "1") (pinfunction "1_1") (pintype "passive"))
      (node (ref "R208") (pin "1") (pinfunction "1_1") (pintype "passive"))
    )
    (net (code "168") (name "VTT64") (class "Default")
      (node (ref "R106") (pin "1") (pinfunction "1_1") (pintype "passive"))
      (node (ref "R107") (pin "1") (pinfunction "1_1") (pintype "passive"))
      (node (ref "R109") (pin "1") (pinfunction "1_1") (pintype "passive"))
      (node (ref "R110") (pin "1") (pinfunction "1_1") (pintype "passive"))
      (node (ref "R112") (pin "1") (pinfunction "1_1") (pintype "passive"))
      (node (ref "R113") (pin "1") (pinfunction "1_1") (pintype "passive"))
    )
    (net (code "169") (name "unconnected-(IC27A-IO_L1N_T0L_N1_DBC_44-PadAE21)") (class "Default")
      (node (ref "IC27") (pin "AE21") (pinfunction "IO_L1N_T0L_N1_DBC_44_AE21") (pintype "bidirectional+no_connect"))
    )
    (net (code "170") (name "unconnected-(IC27C-IO_L1N_T0L_N1_DBC_46-PadAJ26)") (class "Default")
      (node (ref "IC27") (pin "AJ26") (pinfunction "IO_L1N_T0L_N1_DBC_46_AJ26") (pintype "bidirectional+no_connect"))
    )
  )
)
